# MechCherryMXTestBrd.net
KiCad netlist of a schematic drawn in EAGLE
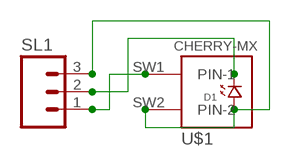
[diagram p0: schematic, sheet 1]

(export (version "E")
  (design (tool "Eeschema 10.0.6"))
  (components
    (comp (ref "D1")
      (value "LED.0805")
      (footprint "eagle-import:0805.LED")
      (libsource (lib "eagle-import") (part "LED.0805"))
    )
    (comp (ref "SL1")
      (value "M03")
      (footprint "eagle-import:03P")
      (libsource (lib "eagle-import") (part "M03"))
    )
    (comp (ref "U$1")
      (value "CHERRY-MX")
      (footprint "eagle-import:CHERRY-MX")
      (libsource (lib "eagle-import") (part "CHERRY-MX"))
    )
  )
  (nets
    (net (code "1") (name "Net-(D1-1)") (class "Default")
      (node (ref "D1") (pin "P$1") (pinfunction "1_P$1") (pintype "bidirectional"))
      (node (ref "SL1") (pin "3") (pinfunction "3_3") (pintype "passive"))
      (node (ref "U$1") (pin "SW2") (pinfunction "PIN-2_SW2") (pintype "bidirectional"))
    )
    (net (code "2") (name "Net-(D1-2)") (class "Default")
      (node (ref "D1") (pin "P$2") (pinfunction "2_P$2") (pintype "bidirectional"))
      (node (ref "SL1") (pin "2") (pinfunction "2_2") (pintype "passive"))
    )
    (net (code "3") (name "Net-(U$1-PIN-1)") (class "Default")
      (node (ref "SL1") (pin "1") (pinfunction "1_1") (pintype "passive"))
      (node (ref "U$1") (pin "SW1") (pinfunction "PIN-1_SW1") (pintype "bidirectional"))
    )
  )
)
